# budzik.net
KiCad netlist of a schematic drawn in Altium Designer
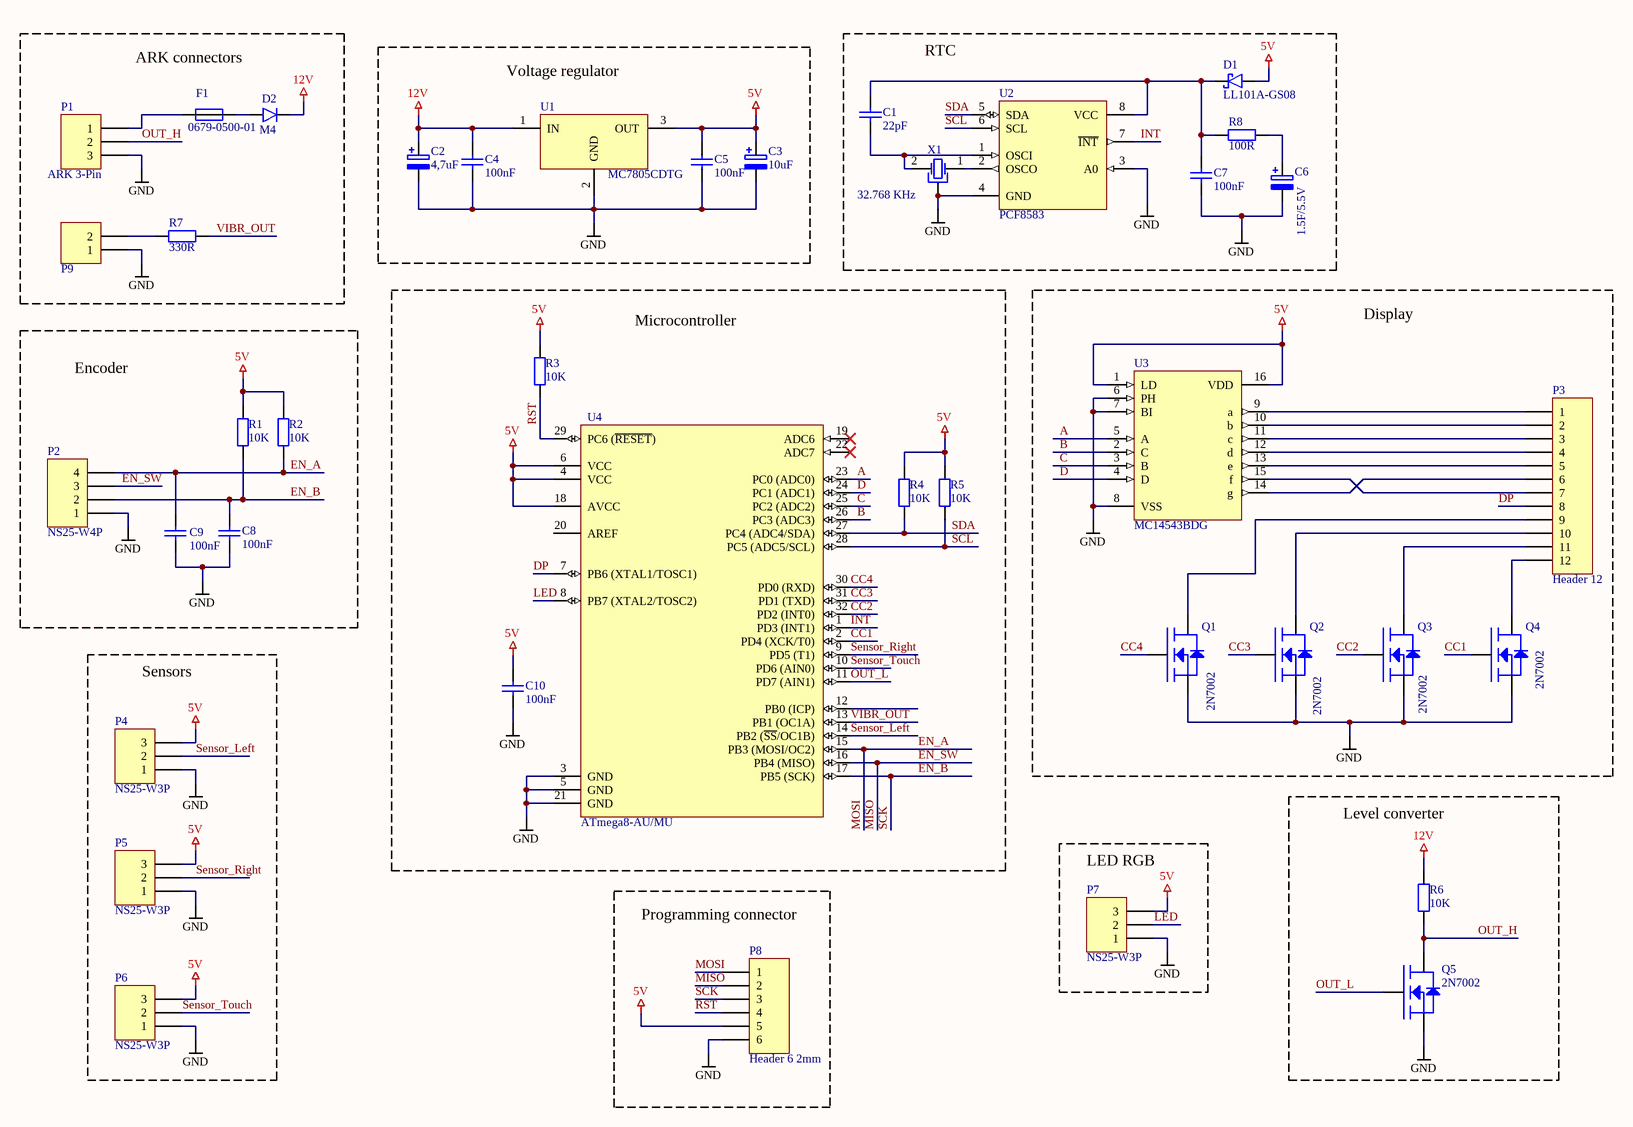
[diagram p0: budzik.SchDoc]

(export (version "E")
  (design (tool "Eeschema 10.0.6"))
  (components
    (comp (ref "C1")
      (value "22pF")
      (footprint "C0805")
      (description "Capacitor")
      (libsource (lib "Schlib1") (part "Cap"))
    )
    (comp (ref "C2")
      (value "4,7uF")
      (footprint "TANC_B")
      (description "Capacitor Polarized")
      (libsource (lib "Library") (part "Cap_Pol"))
    )
    (comp (ref "C3")
      (value "10uF")
      (footprint "TANC_B")
      (description "Capacitor Polarized")
      (libsource (lib "Library") (part "Cap_Pol"))
    )
    (comp (ref "C4")
      (value "100nF")
      (footprint "C0805")
      (description "Capacitor")
      (libsource (lib "Library") (part "Cap"))
    )
    (comp (ref "C5")
      (value "100nF")
      (footprint "C0805")
      (description "Capacitor")
      (libsource (lib "Library") (part "Cap"))
    )
    (comp (ref "C6")
      (value "1.5F/5.5V")
      (footprint "EECS5R5H155")
      (description "Capacitor Polarized")
      (libsource (lib "Library") (part "Cap_Pol"))
    )
    (comp (ref "C7")
      (value "100nF")
      (footprint "C0805")
      (description "Capacitor")
      (libsource (lib "Library") (part "Cap"))
    )
    (comp (ref "C8")
      (value "100nF")
      (footprint "C0805")
      (description "Capacitor")
      (libsource (lib "Library") (part "Cap"))
    )
    (comp (ref "C9")
      (value "100nF")
      (footprint "C0805")
      (description "Capacitor")
      (libsource (lib "Library") (part "Cap"))
    )
    (comp (ref "C10")
      (value "100nF")
      (footprint "C0805")
      (description "Capacitor")
      (libsource (lib "Library") (part "Cap"))
    )
    (comp (ref "D1")
      (value "LL101A-GS08")
      (footprint "SOD80C")
      (libsource (lib "Library") (part "Diode Shottky"))
    )
    (comp (ref "D2") (value "M4") (footprint "SMA") (libsource (lib "Library") (part "Diode")))
    (comp (ref "F1")
      (value "0679-0500-01")
      (footprint "0679-0500-01")
      (description "Bezpiecznik: topikowy; szybki; ceramiczny; 500mA; 125VAC; 125VDC")
      (libsource (lib "Library") (part "0679-0500-01"))
    )
    (comp (ref "P1")
      (value "ARK 3-Pin")
      (footprint "ARK-3.5mm-3pin")
      (libsource (lib "Connectors") (part "ARK 3-Pin"))
    )
    (comp (ref "P2")
      (value "NS25-W4P")
      (footprint "NS25-W4P")
      (libsource (lib "Connectors") (part "NS25-W4P"))
    )
    (comp (ref "P3")
      (value "Header 12")
      (footprint "MA12-1L")
      (description "Header, 12-Pin")
      (libsource (lib "Connectors") (part "Header 12"))
    )
    (comp (ref "P4")
      (value "NS25-W3P")
      (footprint "NS25-W3P")
      (libsource (lib "Connectors") (part "NS25-W3P"))
    )
    (comp (ref "P5")
      (value "NS25-W3P")
      (footprint "NS25-W3P")
      (libsource (lib "Connectors") (part "NS25-W3P"))
    )
    (comp (ref "P6")
      (value "NS25-W3P")
      (footprint "NS25-W3P")
      (libsource (lib "Connectors") (part "NS25-W3P"))
    )
    (comp (ref "P7")
      (value "NS25-W3P")
      (footprint "NS25-W3P")
      (libsource (lib "Connectors") (part "NS25-W3P"))
    )
    (comp (ref "P8")
      (value "Header 6 2mm")
      (footprint "MA06-1_2mm")
      (description "Header, 6-Pin")
      (libsource (lib "Connectors") (part "Header 6"))
    )
    (comp (ref "P9")
      (value "ARK 2-Pin")
      (footprint "ARK-3.5mm-2pin")
      (libsource (lib "Connectors") (part "ARK 2-Pin"))
    )
    (comp (ref "Q1")
      (value "2N7002")
      (footprint "SOT23")
      (description "N-MOSFET")
      (libsource (lib "Library") (part "2N7002(GSD)"))
    )
    (comp (ref "Q2")
      (value "2N7002")
      (footprint "SOT23")
      (description "N-MOSFET")
      (libsource (lib "Library") (part "2N7002(GSD)"))
    )
    (comp (ref "Q3")
      (value "2N7002")
      (footprint "SOT23")
      (description "N-MOSFET")
      (libsource (lib "Library") (part "2N7002(GSD)"))
    )
    (comp (ref "Q4")
      (value "2N7002")
      (footprint "SOT23")
      (description "N-MOSFET")
      (libsource (lib "Library") (part "2N7002(GSD)"))
    )
    (comp (ref "Q5")
      (value "2N7002")
      (footprint "SOT23")
      (description "N-MOSFET")
      (libsource (lib "Library") (part "2N7002(GSD)"))
    )
    (comp (ref "R1")
      (value "10K")
      (footprint "R0805")
      (description "Resistor")
      (libsource (lib "") (part "Res_1"))
    )
    (comp (ref "R2")
      (value "10K")
      (footprint "R0805")
      (description "Resistor")
      (libsource (lib "") (part "Res_1"))
    )
    (comp (ref "R3")
      (value "10K")
      (footprint "R0805")
      (description "Resistor")
      (libsource (lib "") (part "Res_2"))
    )
    (comp (ref "R4")
      (value "10K")
      (footprint "R0805")
      (description "Resistor")
      (libsource (lib "altium-import") (part "root_1_Res_"))
    )
    (comp (ref "R5")
      (value "10K")
      (footprint "R0805")
      (description "Resistor")
      (libsource (lib "altium-import") (part "root_1_Res_"))
    )
    (comp (ref "R6")
      (value "10K")
      (footprint "R0805")
      (description "Resistor")
      (libsource (lib "") (part "Res_1"))
    )
    (comp (ref "R7")
      (value "330R")
      (footprint "R0805")
      (description "Resistor")
      (libsource (lib "Library") (part "Res"))
    )
    (comp (ref "R8")
      (value "100R")
      (footprint "R0805")
      (description "Resistor")
      (libsource (lib "") (part "Res_3"))
    )
    (comp (ref "U1") (value "MC7805CDTG") (footprint "TO-252") (libsource (lib "IC") (part "78xx")))
    (comp (ref "U2") (value "PCF8583") (footprint "SO-8T") (libsource (lib "IC") (part "PCF8583")))
    (comp (ref "U3")
      (value "MC14543BDG")
      (footprint "SO-16")
      (description "BCD na 7 segmentowy")
      (libsource (lib "IC") (part "MC14543BDG"))
    )
    (comp (ref "U4")
      (value "ATmega8-AU/MU")
      (footprint "TQFP-32A")
      (description "TQFP - 32pin / MLF - 32pin")
      (libsource (lib "IC") (part "ATmega8-AU/MU"))
    )
    (comp (ref "X1")
      (value "32.768 KHz")
      (footprint "TC26_V")
      (libsource (lib "Library") (part "Crystal _GND"))
    )
  )
  (nets
    (net (code "1") (name "/A") (class "Default")
      (node (ref "U3") (pin "5") (pinfunction "A_5") (pintype "input"))
      (node (ref "U4") (pin "23") (pinfunction "PC0_(ADC0)_23") (pintype "bidirectional"))
    )
    (net (code "2") (name "/B") (class "Default")
      (node (ref "U3") (pin "2") (pinfunction "C_2") (pintype "input"))
      (node (ref "U4") (pin "26") (pinfunction "PC3_(ADC3)_26") (pintype "bidirectional"))
    )
    (net (code "3") (name "/C") (class "Default")
      (node (ref "U3") (pin "3") (pinfunction "B_3") (pintype "input"))
      (node (ref "U4") (pin "25") (pinfunction "PC2_(ADC2)_25") (pintype "bidirectional"))
    )
    (net (code "4") (name "/CC1") (class "Default")
      (node (ref "Q4") (pin "1") (pinfunction "G_1") (pintype "passive"))
      (node (ref "U4") (pin "2") (pinfunction "PD4_(XCK/T0)_2") (pintype "bidirectional"))
    )
    (net (code "5") (name "/CC2") (class "Default")
      (node (ref "Q3") (pin "1") (pinfunction "G_1") (pintype "passive"))
      (node (ref "U4") (pin "32") (pinfunction "PD2_(INT0)_32") (pintype "bidirectional"))
    )
    (net (code "6") (name "/CC3") (class "Default")
      (node (ref "Q2") (pin "1") (pinfunction "G_1") (pintype "passive"))
      (node (ref "U4") (pin "31") (pinfunction "PD1_(TXD)_31") (pintype "bidirectional"))
    )
    (net (code "7") (name "/CC4") (class "Default")
      (node (ref "Q1") (pin "1") (pinfunction "G_1") (pintype "passive"))
      (node (ref "U4") (pin "30") (pinfunction "PD0_(RXD)_30") (pintype "bidirectional"))
    )
    (net (code "8") (name "/D") (class "Default")
      (node (ref "U3") (pin "4") (pinfunction "D_4") (pintype "input"))
      (node (ref "U4") (pin "24") (pinfunction "PC1_(ADC1)_24") (pintype "bidirectional"))
    )
    (net (code "9") (name "/DP") (class "Default")
      (node (ref "P3") (pin "8") (pinfunction "8_8") (pintype "passive"))
      (node (ref "U4") (pin "7") (pinfunction "PB6_(XTAL1/TOSC1)_7") (pintype "bidirectional"))
    )
    (net (code "10") (name "/EN_A") (class "Default")
      (node (ref "C9") (pin "1") (pinfunction "1_1") (pintype "passive"))
      (node (ref "P2") (pin "4") (pinfunction "4_4") (pintype "passive"))
      (node (ref "P8") (pin "1") (pinfunction "1_1") (pintype "passive"))
      (node (ref "R2") (pin "1") (pinfunction "1_1") (pintype "passive"))
      (node (ref "U4") (pin "15") (pinfunction "PB3_(MOSI/OC2)_15") (pintype "bidirectional"))
    )
    (net (code "11") (name "/EN_B") (class "Default")
      (node (ref "C8") (pin "1") (pinfunction "1_1") (pintype "passive"))
      (node (ref "P2") (pin "2") (pinfunction "2_2") (pintype "passive"))
      (node (ref "P8") (pin "3") (pinfunction "3_3") (pintype "passive"))
      (node (ref "R1") (pin "1") (pinfunction "1_1") (pintype "passive"))
      (node (ref "U4") (pin "17") (pinfunction "PB5_(SCK)_17") (pintype "bidirectional"))
    )
    (net (code "12") (name "/EN_SW") (class "Default")
      (node (ref "P2") (pin "3") (pinfunction "3_3") (pintype "passive"))
      (node (ref "P8") (pin "2") (pinfunction "2_2") (pintype "passive"))
      (node (ref "U4") (pin "16") (pinfunction "PB4_(MISO)_16") (pintype "bidirectional"))
    )
    (net (code "13") (name "/INT") (class "Default")
      (node (ref "U2") (pin "7") (pinfunction "~{INT}_7") (pintype "output"))
      (node (ref "U4") (pin "1") (pinfunction "PD3_(INT1)_1") (pintype "bidirectional"))
    )
    (net (code "14") (name "/LED") (class "Default")
      (node (ref "P7") (pin "2") (pinfunction "2_2") (pintype "passive"))
      (node (ref "U4") (pin "8") (pinfunction "PB7_(XTAL2/TOSC2)_8") (pintype "bidirectional"))
    )
    (net (code "15") (name "/OUT_H") (class "Default")
      (node (ref "P1") (pin "2") (pinfunction "2_2") (pintype "passive"))
      (node (ref "Q5") (pin "3") (pinfunction "D_3") (pintype "passive"))
      (node (ref "R6") (pin "1") (pinfunction "1_1") (pintype "passive"))
    )
    (net (code "16") (name "/OUT_L") (class "Default")
      (node (ref "Q5") (pin "1") (pinfunction "G_1") (pintype "passive"))
      (node (ref "U4") (pin "11") (pinfunction "PD7_(AIN1)_11") (pintype "bidirectional"))
    )
    (net (code "17") (name "/RST") (class "Default")
      (node (ref "P8") (pin "4") (pinfunction "4_4") (pintype "passive"))
      (node (ref "R3") (pin "2") (pinfunction "2_2") (pintype "passive"))
      (node (ref "U4") (pin "29") (pinfunction "PC6_(~{RESET})_29") (pintype "bidirectional"))
    )
    (net (code "18") (name "/SCL") (class "Default")
      (node (ref "R5") (pin "1") (pinfunction "1_1") (pintype "passive"))
      (node (ref "U2") (pin "6") (pinfunction "SCL_6") (pintype "input"))
      (node (ref "U4") (pin "28") (pinfunction "PC5_(ADC5/SCL)_28") (pintype "bidirectional"))
    )
    (net (code "19") (name "/SDA") (class "Default")
      (node (ref "R4") (pin "1") (pinfunction "1_1") (pintype "passive"))
      (node (ref "U2") (pin "5") (pinfunction "SDA_5") (pintype "bidirectional"))
      (node (ref "U4") (pin "27") (pinfunction "PC4_(ADC4/SDA)_27") (pintype "bidirectional"))
    )
    (net (code "20") (name "/Sensor_Left") (class "Default")
      (node (ref "P4") (pin "2") (pinfunction "2_2") (pintype "passive"))
      (node (ref "U4") (pin "14") (pinfunction "PB2_(~{SS}/OC1B)_14") (pintype "bidirectional"))
    )
    (net (code "21") (name "/Sensor_Right") (class "Default")
      (node (ref "P5") (pin "2") (pinfunction "2_2") (pintype "passive"))
      (node (ref "U4") (pin "9") (pinfunction "PD5_(T1)_9") (pintype "bidirectional"))
    )
    (net (code "22") (name "/Sensor_Touch") (class "Default")
      (node (ref "P6") (pin "2") (pinfunction "2_2") (pintype "passive"))
      (node (ref "U4") (pin "10") (pinfunction "PD6_(AIN0)_10") (pintype "bidirectional"))
    )
    (net (code "23") (name "/VIBR_OUT") (class "Default")
      (node (ref "R7") (pin "1") (pinfunction "1_1") (pintype "passive"))
      (node (ref "U4") (pin "13") (pinfunction "PB1_(OC1A)_13") (pintype "bidirectional"))
    )
    (net (code "24") (name "5V") (class "Default")
      (node (ref "C10") (pin "1") (pinfunction "1_1") (pintype "passive"))
      (node (ref "C3") (pin "1") (pinfunction "1_1") (pintype "passive"))
      (node (ref "C5") (pin "1") (pinfunction "1_1") (pintype "passive"))
      (node (ref "D1") (pin "2") (pinfunction "2_2") (pintype "power_in"))
      (node (ref "P4") (pin "3") (pinfunction "3_3") (pintype "passive"))
      (node (ref "P5") (pin "3") (pinfunction "3_3") (pintype "passive"))
      (node (ref "P6") (pin "3") (pinfunction "3_3") (pintype "passive"))
      (node (ref "P7") (pin "3") (pinfunction "3_3") (pintype "passive"))
      (node (ref "P8") (pin "5") (pinfunction "5_5") (pintype "passive"))
      (node (ref "R1") (pin "2") (pinfunction "2_2") (pintype "passive"))
      (node (ref "R2") (pin "2") (pinfunction "2_2") (pintype "passive"))
      (node (ref "R3") (pin "1") (pinfunction "1_1") (pintype "passive"))
      (node (ref "R4") (pin "2") (pinfunction "2_2") (pintype "passive"))
      (node (ref "R5") (pin "2") (pinfunction "2_2") (pintype "passive"))
      (node (ref "U1") (pin "3") (pinfunction "OUT_3") (pintype "power_in"))
      (node (ref "U3") (pin "1") (pinfunction "LD_1") (pintype "input"))
      (node (ref "U3") (pin "16") (pinfunction "VDD_16") (pintype "power_in"))
      (node (ref "U4") (pin "18") (pinfunction "AVCC_18") (pintype "power_in"))
      (node (ref "U4") (pin "4") (pinfunction "VCC_4") (pintype "power_in"))
      (node (ref "U4") (pin "6") (pinfunction "VCC_6") (pintype "power_in"))
    )
    (net (code "25") (name "12V") (class "Default")
      (node (ref "C2") (pin "1") (pinfunction "1_1") (pintype "passive"))
      (node (ref "C4") (pin "1") (pinfunction "1_1") (pintype "passive"))
      (node (ref "D2") (pin "1") (pinfunction "1_1") (pintype "power_in"))
      (node (ref "R6") (pin "2") (pinfunction "2_2") (pintype "passive"))
      (node (ref "U1") (pin "1") (pinfunction "IN_1") (pintype "power_in"))
    )
    (net (code "26") (name "GND") (class "Default")
      (node (ref "C10") (pin "2") (pinfunction "2_2") (pintype "passive"))
      (node (ref "C2") (pin "2") (pinfunction "2_2") (pintype "passive"))
      (node (ref "C3") (pin "2") (pinfunction "2_2") (pintype "passive"))
      (node (ref "C4") (pin "2") (pinfunction "2_2") (pintype "passive"))
      (node (ref "C5") (pin "2") (pinfunction "2_2") (pintype "passive"))
      (node (ref "C6") (pin "2") (pinfunction "2_2") (pintype "passive"))
      (node (ref "C7") (pin "2") (pinfunction "2_2") (pintype "passive"))
      (node (ref "C8") (pin "2") (pinfunction "2_2") (pintype "passive"))
      (node (ref "C9") (pin "2") (pinfunction "2_2") (pintype "passive"))
      (node (ref "P1") (pin "3") (pinfunction "3_3") (pintype "passive"))
      (node (ref "P2") (pin "1") (pinfunction "1_1") (pintype "passive"))
      (node (ref "P4") (pin "1") (pinfunction "1_1") (pintype "passive"))
      (node (ref "P5") (pin "1") (pinfunction "1_1") (pintype "passive"))
      (node (ref "P6") (pin "1") (pinfunction "1_1") (pintype "passive"))
      (node (ref "P7") (pin "1") (pinfunction "1_1") (pintype "passive"))
      (node (ref "P8") (pin "6") (pinfunction "6_6") (pintype "passive"))
      (node (ref "P9") (pin "1") (pinfunction "1_1") (pintype "passive"))
      (node (ref "Q1") (pin "2") (pinfunction "S_2") (pintype "passive"))
      (node (ref "Q2") (pin "2") (pinfunction "S_2") (pintype "passive"))
      (node (ref "Q3") (pin "2") (pinfunction "S_2") (pintype "passive"))
      (node (ref "Q4") (pin "2") (pinfunction "S_2") (pintype "passive"))
      (node (ref "Q5") (pin "2") (pinfunction "S_2") (pintype "passive"))
      (node (ref "U1") (pin "2") (pinfunction "GND_2") (pintype "power_in"))
      (node (ref "U2") (pin "3") (pinfunction "A0_3") (pintype "input"))
      (node (ref "U2") (pin "4") (pinfunction "GND_4") (pintype "power_in"))
      (node (ref "U3") (pin "6") (pinfunction "PH_6") (pintype "input"))
      (node (ref "U3") (pin "7") (pinfunction "BI_7") (pintype "input"))
      (node (ref "U3") (pin "8") (pinfunction "VSS_8") (pintype "power_in"))
      (node (ref "U4") (pin "21") (pinfunction "GND_21") (pintype "power_in"))
      (node (ref "U4") (pin "3") (pinfunction "GND_3") (pintype "power_in"))
      (node (ref "U4") (pin "5") (pinfunction "GND_5") (pintype "power_in"))
      (node (ref "X1") (pin "3") (pinfunction "3_3") (pintype "passive"))
    )
    (net (code "27") (name "Net-(C6-Pad1)") (class "Default")
      (node (ref "C6") (pin "1") (pinfunction "1_1") (pintype "passive"))
      (node (ref "R8") (pin "2") (pinfunction "2_2") (pintype "passive"))
    )
    (net (code "28") (name "Net-(D2-Pad2)") (class "Default")
      (node (ref "D2") (pin "2") (pinfunction "2_2") (pintype "power_in"))
      (node (ref "F1") (pin "2") (pinfunction "2_2") (pintype "passive"))
    )
    (net (code "29") (name "Net-(F1-Pad1)") (class "Default")
      (node (ref "F1") (pin "1") (pinfunction "1_1") (pintype "passive"))
      (node (ref "P1") (pin "1") (pinfunction "1_1") (pintype "passive"))
    )
    (net (code "30") (name "Net-(P9-Pad2)") (class "Default")
      (node (ref "P9") (pin "2") (pinfunction "2_2") (pintype "passive"))
      (node (ref "R7") (pin "2") (pinfunction "2_2") (pintype "passive"))
    )
    (net (code "31") (name "Net-(Q1-D)") (class "Default")
      (node (ref "P3") (pin "9") (pinfunction "9_9") (pintype "passive"))
      (node (ref "Q1") (pin "3") (pinfunction "D_3") (pintype "passive"))
    )
    (net (code "32") (name "Net-(Q2-D)") (class "Default")
      (node (ref "P3") (pin "10") (pinfunction "10_10") (pintype "passive"))
      (node (ref "Q2") (pin "3") (pinfunction "D_3") (pintype "passive"))
    )
    (net (code "33") (name "Net-(Q3-D)") (class "Default")
      (node (ref "P3") (pin "11") (pinfunction "11_11") (pintype "passive"))
      (node (ref "Q3") (pin "3") (pinfunction "D_3") (pintype "passive"))
    )
    (net (code "34") (name "Net-(Q4-D)") (class "Default")
      (node (ref "P3") (pin "12") (pinfunction "12_12") (pintype "passive"))
      (node (ref "Q4") (pin "3") (pinfunction "D_3") (pintype "passive"))
    )
    (net (code "35") (name "Net-(U2-OSCI)") (class "Default")
      (node (ref "C1") (pin "2") (pinfunction "2_2") (pintype "passive"))
      (node (ref "U2") (pin "1") (pinfunction "OSCI_1") (pintype "input"))
      (node (ref "X1") (pin "2") (pinfunction "2_2") (pintype "passive"))
    )
    (net (code "36") (name "Net-(U2-OSCO)") (class "Default")
      (node (ref "U2") (pin "2") (pinfunction "OSCO_2") (pintype "output"))
      (node (ref "X1") (pin "1") (pinfunction "1_1") (pintype "passive"))
    )
    (net (code "37") (name "Net-(U2-VCC)") (class "Default")
      (node (ref "C1") (pin "1") (pinfunction "1_1") (pintype "passive"))
      (node (ref "C7") (pin "1") (pinfunction "1_1") (pintype "passive"))
      (node (ref "D1") (pin "1") (pinfunction "1_1") (pintype "power_in"))
      (node (ref "R8") (pin "1") (pinfunction "1_1") (pintype "passive"))
      (node (ref "U2") (pin "8") (pinfunction "VCC_8") (pintype "power_in"))
    )
    (net (code "38") (name "Net-(U3-a)") (class "Default")
      (node (ref "P3") (pin "1") (pinfunction "1_1") (pintype "passive"))
      (node (ref "U3") (pin "9") (pinfunction "a_9") (pintype "output"))
    )
    (net (code "39") (name "Net-(U3-b)") (class "Default")
      (node (ref "P3") (pin "2") (pinfunction "2_2") (pintype "passive"))
      (node (ref "U3") (pin "10") (pinfunction "b_10") (pintype "output"))
    )
    (net (code "40") (name "Net-(U3-c)") (class "Default")
      (node (ref "P3") (pin "3") (pinfunction "3_3") (pintype "passive"))
      (node (ref "U3") (pin "11") (pinfunction "c_11") (pintype "output"))
    )
    (net (code "41") (name "Net-(U3-d)") (class "Default")
      (node (ref "P3") (pin "4") (pinfunction "4_4") (pintype "passive"))
      (node (ref "U3") (pin "12") (pinfunction "d_12") (pintype "output"))
    )
    (net (code "42") (name "Net-(U3-e)") (class "Default")
      (node (ref "P3") (pin "5") (pinfunction "5_5") (pintype "passive"))
      (node (ref "U3") (pin "13") (pinfunction "e_13") (pintype "output"))
    )
    (net (code "43") (name "Net-(U3-f)") (class "Default")
      (node (ref "P3") (pin "7") (pinfunction "7_7") (pintype "passive"))
      (node (ref "U3") (pin "15") (pinfunction "f_15") (pintype "output"))
    )
    (net (code "44") (name "Net-(U3-g)") (class "Default")
      (node (ref "P3") (pin "6") (pinfunction "6_6") (pintype "passive"))
      (node (ref "U3") (pin "14") (pinfunction "g_14") (pintype "output"))
    )
    (net (code "45") (name "unconnected-(U4-ADC6-Pad19)") (class "Default")
      (node (ref "U4") (pin "19") (pinfunction "ADC6_19") (pintype "input+no_connect"))
    )
    (net (code "46") (name "unconnected-(U4-ADC7-Pad22)") (class "Default")
      (node (ref "U4") (pin "22") (pinfunction "ADC7_22") (pintype "input+no_connect"))
    )
    (net (code "47") (name "unconnected-(U4-AREF-Pad20)") (class "Default")
      (node (ref "U4") (pin "20") (pinfunction "AREF_20") (pintype "passive"))
    )
    (net (code "48") (name "unconnected-(U4-PB0_(ICP)-Pad12)") (class "Default")
      (node (ref "U4") (pin "12") (pinfunction "PB0_(ICP)_12") (pintype "bidirectional"))
    )
  )
)
